# ioboard.net
KiCad netlist of a schematic drawn in EAGLE
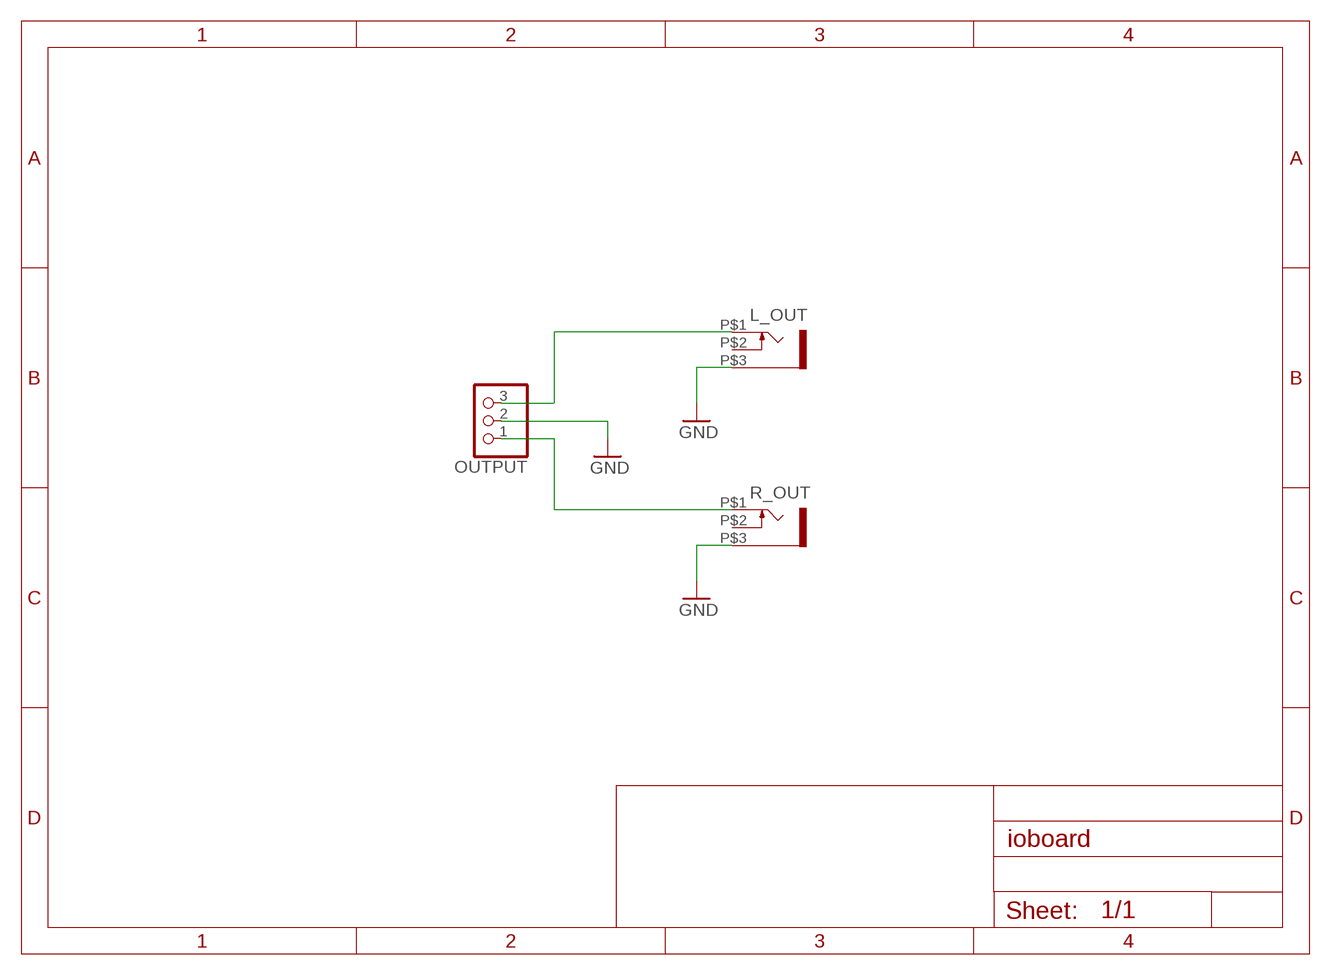
[diagram p0: schematic, sheet 1]

(export (version "E")
  (design (tool "Eeschema 10.0.6"))
  (components
    (comp (ref "L_OUT")
      (value "WQP-PJ301M-12_JACK")
      (footprint "eagle-import:WQP-PJ301M-12_JACK")
      (libsource (lib "eagle-import") (part "WQP-PJ301M-12_JACK"))
    )
    (comp (ref "OUTPUT")
      (value "PINHD-1X3")
      (footprint "eagle-import:1X03")
      (libsource (lib "eagle-import") (part "PINHD-1X3"))
    )
    (comp (ref "R_OUT")
      (value "WQP-PJ301M-12_JACK")
      (footprint "eagle-import:WQP-PJ301M-12_JACK")
      (libsource (lib "eagle-import") (part "WQP-PJ301M-12_JACK"))
    )
  )
  (nets
    (net (code "1") (name "GND") (class "Default")
      (node (ref "L_OUT") (pin "P$3") (pinfunction "1_P$3") (pintype "passive"))
      (node (ref "OUTPUT") (pin "2") (pinfunction "2_2") (pintype "passive"))
      (node (ref "R_OUT") (pin "P$3") (pinfunction "1_P$3") (pintype "passive"))
    )
    (net (code "2") (name "Net-(L_OUT-2)") (class "Default")
      (node (ref "L_OUT") (pin "P$1") (pinfunction "2_P$1") (pintype "passive"))
      (node (ref "OUTPUT") (pin "3") (pinfunction "3_3") (pintype "passive"))
    )
    (net (code "3") (name "Net-(R_OUT-2)") (class "Default")
      (node (ref "OUTPUT") (pin "1") (pinfunction "1_1") (pintype "passive"))
      (node (ref "R_OUT") (pin "P$1") (pinfunction "2_P$1") (pintype "passive"))
    )
    (net (code "4") (name "unconnected-(L_OUT-3-PadP$2)") (class "Default")
      (node (ref "L_OUT") (pin "P$2") (pinfunction "3_P$2") (pintype "passive"))
    )
    (net (code "5") (name "unconnected-(R_OUT-3-PadP$2)") (class "Default")
      (node (ref "R_OUT") (pin "P$2") (pinfunction "3_P$2") (pintype "passive"))
    )
  )
)
